# AFE_Pants_Powered.net
KiCad netlist of a schematic drawn in EAGLE
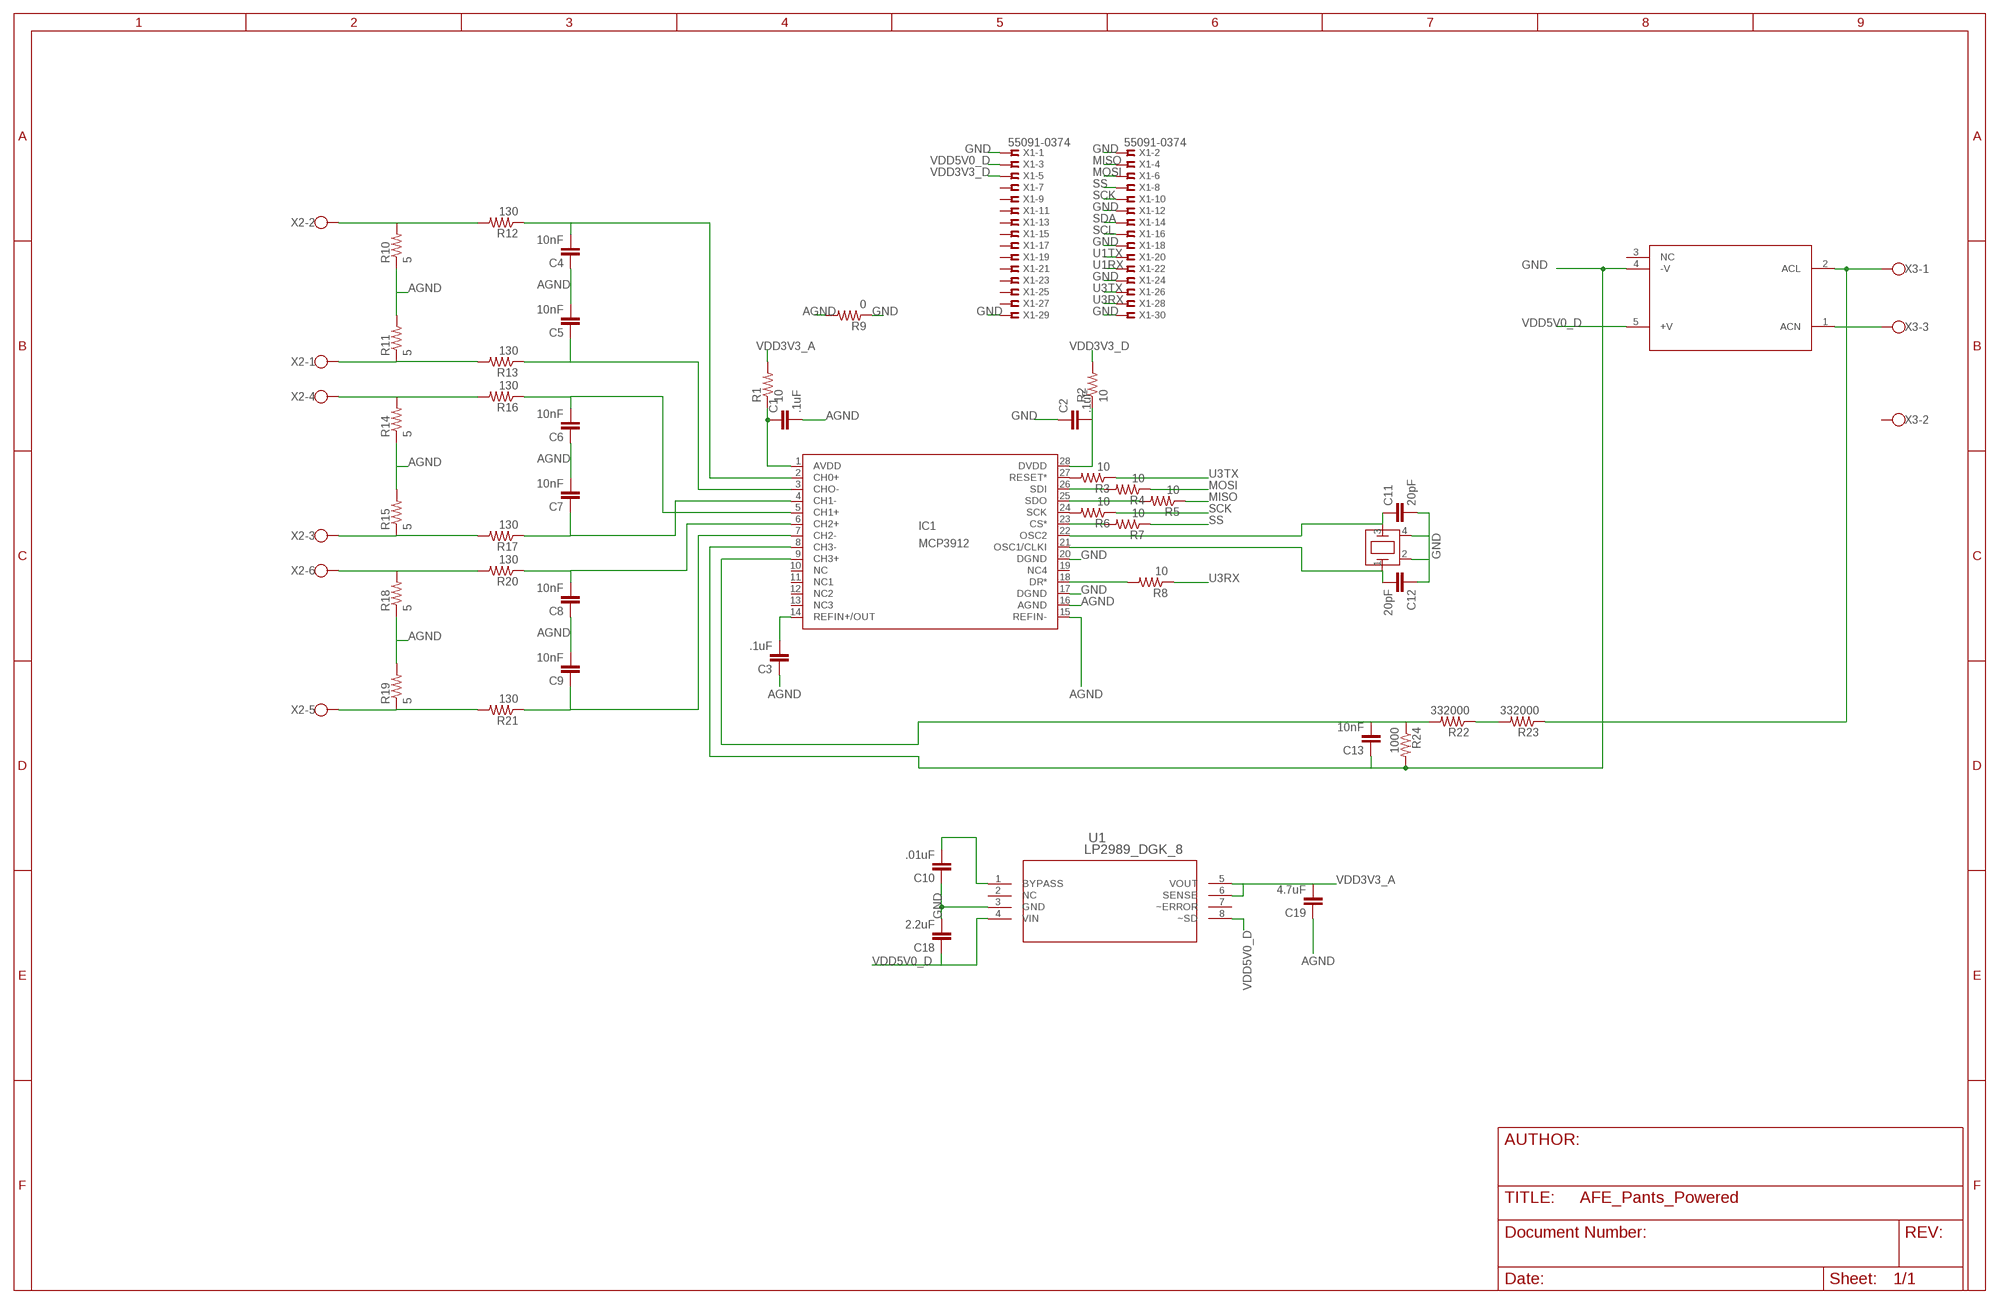
[diagram p0: schematic, sheet 1]

(export (version "E")
  (design (tool "Eeschema 10.0.6"))
  (components
    (comp (ref "C1")
      (value ".1uF")
      (footprint "eagle-import:0805")
      (libsource (lib "eagle-import") (part "CAP0805"))
    )
    (comp (ref "C2")
      (value ".1uF")
      (footprint "eagle-import:0805")
      (libsource (lib "eagle-import") (part "CAP0805"))
    )
    (comp (ref "C3")
      (value ".1uF")
      (footprint "eagle-import:0805")
      (libsource (lib "eagle-import") (part "CAP0805"))
    )
    (comp (ref "C4")
      (value "10nF")
      (footprint "eagle-import:0805")
      (libsource (lib "eagle-import") (part "CAP0805"))
    )
    (comp (ref "C5")
      (value "10nF")
      (footprint "eagle-import:0805")
      (libsource (lib "eagle-import") (part "CAP0805"))
    )
    (comp (ref "C6")
      (value "10nF")
      (footprint "eagle-import:0805")
      (libsource (lib "eagle-import") (part "CAP0805"))
    )
    (comp (ref "C7")
      (value "10nF")
      (footprint "eagle-import:0805")
      (libsource (lib "eagle-import") (part "CAP0805"))
    )
    (comp (ref "C8")
      (value "10nF")
      (footprint "eagle-import:0805")
      (libsource (lib "eagle-import") (part "CAP0805"))
    )
    (comp (ref "C9")
      (value "10nF")
      (footprint "eagle-import:0805")
      (libsource (lib "eagle-import") (part "CAP0805"))
    )
    (comp (ref "C10")
      (value ".01uF")
      (footprint "eagle-import:0805")
      (libsource (lib "eagle-import") (part "CAP0805"))
    )
    (comp (ref "C11")
      (value "20pF")
      (footprint "eagle-import:0805")
      (libsource (lib "eagle-import") (part "CAP0805"))
    )
    (comp (ref "C12")
      (value "20pF")
      (footprint "eagle-import:0805")
      (libsource (lib "eagle-import") (part "CAP0805"))
    )
    (comp (ref "C13")
      (value "10nF")
      (footprint "eagle-import:0805")
      (libsource (lib "eagle-import") (part "CAP0805"))
    )
    (comp (ref "C18")
      (value "2.2uF")
      (footprint "eagle-import:0805")
      (libsource (lib "eagle-import") (part "CAP0805"))
    )
    (comp (ref "C19")
      (value "4.7uF")
      (footprint "eagle-import:0805")
      (libsource (lib "eagle-import") (part "CAP0805"))
    )
    (comp (ref "IC1")
      (value "MCP3912")
      (footprint "eagle-import:SSOP28")
      (libsource (lib "eagle-import") (part "MCP3912"))
    )
    (comp (ref "R1")
      (value "10")
      (footprint "eagle-import:0805")
      (libsource (lib "eagle-import") (part "RESISTOR0805-RES"))
    )
    (comp (ref "R2")
      (value "10")
      (footprint "eagle-import:0805")
      (libsource (lib "eagle-import") (part "RESISTOR0805-RES"))
    )
    (comp (ref "R3")
      (value "10")
      (footprint "eagle-import:0805")
      (libsource (lib "eagle-import") (part "RESISTOR0805-RES"))
    )
    (comp (ref "R4")
      (value "10")
      (footprint "eagle-import:0805")
      (libsource (lib "eagle-import") (part "RESISTOR0805-RES"))
    )
    (comp (ref "R5")
      (value "10")
      (footprint "eagle-import:0805")
      (libsource (lib "eagle-import") (part "RESISTOR0805-RES"))
    )
    (comp (ref "R6")
      (value "10")
      (footprint "eagle-import:0805")
      (libsource (lib "eagle-import") (part "RESISTOR0805-RES"))
    )
    (comp (ref "R7")
      (value "10")
      (footprint "eagle-import:0805")
      (libsource (lib "eagle-import") (part "RESISTOR0805-RES"))
    )
    (comp (ref "R8")
      (value "10")
      (footprint "eagle-import:0805")
      (libsource (lib "eagle-import") (part "RESISTOR0805-RES"))
    )
    (comp (ref "R9")
      (value "0")
      (footprint "eagle-import:0805")
      (libsource (lib "eagle-import") (part "RESISTOR0805-RES"))
    )
    (comp (ref "R10")
      (value "5")
      (footprint "eagle-import:0805")
      (libsource (lib "eagle-import") (part "RESISTOR0805-RES"))
    )
    (comp (ref "R11")
      (value "5")
      (footprint "eagle-import:0805")
      (libsource (lib "eagle-import") (part "RESISTOR0805-RES"))
    )
    (comp (ref "R12")
      (value "130")
      (footprint "eagle-import:0805")
      (libsource (lib "eagle-import") (part "RESISTOR0805-RES"))
    )
    (comp (ref "R13")
      (value "130")
      (footprint "eagle-import:0805")
      (libsource (lib "eagle-import") (part "RESISTOR0805-RES"))
    )
    (comp (ref "R14")
      (value "5")
      (footprint "eagle-import:0805")
      (libsource (lib "eagle-import") (part "RESISTOR0805-RES"))
    )
    (comp (ref "R15")
      (value "5")
      (footprint "eagle-import:0805")
      (libsource (lib "eagle-import") (part "RESISTOR0805-RES"))
    )
    (comp (ref "R16")
      (value "130")
      (footprint "eagle-import:0805")
      (libsource (lib "eagle-import") (part "RESISTOR0805-RES"))
    )
    (comp (ref "R17")
      (value "130")
      (footprint "eagle-import:0805")
      (libsource (lib "eagle-import") (part "RESISTOR0805-RES"))
    )
    (comp (ref "R18")
      (value "5")
      (footprint "eagle-import:0805")
      (libsource (lib "eagle-import") (part "RESISTOR0805-RES"))
    )
    (comp (ref "R19")
      (value "5")
      (footprint "eagle-import:0805")
      (libsource (lib "eagle-import") (part "RESISTOR0805-RES"))
    )
    (comp (ref "R20")
      (value "130")
      (footprint "eagle-import:0805")
      (libsource (lib "eagle-import") (part "RESISTOR0805-RES"))
    )
    (comp (ref "R21")
      (value "130")
      (footprint "eagle-import:0805")
      (libsource (lib "eagle-import") (part "RESISTOR0805-RES"))
    )
    (comp (ref "R22")
      (value "332000")
      (footprint "eagle-import:0805")
      (libsource (lib "eagle-import") (part "RESISTOR0805-RES"))
    )
    (comp (ref "R23")
      (value "332000")
      (footprint "eagle-import:0805")
      (libsource (lib "eagle-import") (part "RESISTOR0805-RES"))
    )
    (comp (ref "R24")
      (value "1000")
      (footprint "eagle-import:0805")
      (libsource (lib "eagle-import") (part "RESISTOR0805-RES"))
    )
    (comp (ref "U$1")
      (value "7M-12.000MEEQ-T")
      (footprint "eagle-import:7M-CRYSTAL")
      (libsource (lib "eagle-import") (part "7M-12.000MEEQ-T"))
    )
    (comp (ref "U$2")
      (value "ECE05US05")
      (footprint "eagle-import:ECE05US05")
      (libsource (lib "eagle-import") (part "ECE05US05"))
    )
    (comp (ref "U1")
      (value "LP2989_DGK_8")
      (footprint "eagle-import:MUA08A")
      (fields (field (name "PARTNUMBER") "LP2989AIMM-25"))
      (libsource (lib "eagle-import") (part "LP2989_DGK_8"))
    )
    (comp (ref "X1")
      (value "55091-0374")
      (footprint "eagle-import:55091-0374")
      (libsource (lib "eagle-import") (part "55091-0374"))
    )
    (comp (ref "X2")
      (value "W237-6")
      (footprint "eagle-import:W237-6")
      (libsource (lib "eagle-import") (part "W237-6"))
    )
    (comp (ref "X3")
      (value "W237-103")
      (footprint "eagle-import:W237-103")
      (fields (field (name "MPN") "237-103"))
      (libsource (lib "eagle-import") (part "W237-103"))
    )
  )
  (nets
    (net (code "1") (name "/AGND") (class "Default")
      (node (ref "C1") (pin "2") (pinfunction "2_2") (pintype "passive"))
      (node (ref "C19") (pin "1") (pinfunction "1_1") (pintype "passive"))
      (node (ref "C3") (pin "1") (pinfunction "1_1") (pintype "passive"))
      (node (ref "C4") (pin "1") (pinfunction "1_1") (pintype "passive"))
      (node (ref "C5") (pin "2") (pinfunction "2_2") (pintype "passive"))
      (node (ref "C6") (pin "1") (pinfunction "1_1") (pintype "passive"))
      (node (ref "C7") (pin "2") (pinfunction "2_2") (pintype "passive"))
      (node (ref "C8") (pin "1") (pinfunction "1_1") (pintype "passive"))
      (node (ref "C9") (pin "2") (pinfunction "2_2") (pintype "passive"))
      (node (ref "IC1") (pin "15") (pinfunction "REFIN-_15") (pintype "bidirectional"))
      (node (ref "IC1") (pin "16") (pinfunction "AGND_16") (pintype "bidirectional"))
      (node (ref "R10") (pin "1") (pinfunction "1_1") (pintype "passive"))
      (node (ref "R11") (pin "2") (pinfunction "2_2") (pintype "passive"))
      (node (ref "R14") (pin "1") (pinfunction "1_1") (pintype "passive"))
      (node (ref "R15") (pin "2") (pinfunction "2_2") (pintype "passive"))
      (node (ref "R18") (pin "1") (pinfunction "1_1") (pintype "passive"))
      (node (ref "R19") (pin "2") (pinfunction "2_2") (pintype "passive"))
      (node (ref "R9") (pin "2") (pinfunction "2_2") (pintype "passive"))
    )
    (net (code "2") (name "/GND") (class "Default")
      (node (ref "C10") (pin "1") (pinfunction "1_1") (pintype "passive"))
      (node (ref "C11") (pin "2") (pinfunction "2_2") (pintype "passive"))
      (node (ref "C12") (pin "1") (pinfunction "1_1") (pintype "passive"))
      (node (ref "C13") (pin "1") (pinfunction "1_1") (pintype "passive"))
      (node (ref "C18") (pin "2") (pinfunction "2_2") (pintype "passive"))
      (node (ref "C2") (pin "1") (pinfunction "1_1") (pintype "passive"))
      (node (ref "IC1") (pin "17") (pinfunction "DGND_17") (pintype "bidirectional"))
      (node (ref "IC1") (pin "20") (pinfunction "DGND_20") (pintype "bidirectional"))
      (node (ref "IC1") (pin "8") (pinfunction "CH3-_8") (pintype "bidirectional"))
      (node (ref "R24") (pin "2") (pinfunction "2_2") (pintype "passive"))
      (node (ref "R9") (pin "1") (pinfunction "1_1") (pintype "passive"))
      (node (ref "U$1") (pin "2") (pinfunction "GND1_2") (pintype "bidirectional"))
      (node (ref "U$1") (pin "4") (pinfunction "GND2_4") (pintype "bidirectional"))
      (node (ref "U$2") (pin "4") (pinfunction "-V_4") (pintype "bidirectional"))
      (node (ref "U1") (pin "3") (pinfunction "GND_3") (pintype "passive"))
      (node (ref "X1") (pin "1") (pinfunction "S_1") (pintype "passive"))
      (node (ref "X1") (pin "12") (pinfunction "S_12") (pintype "passive"))
      (node (ref "X1") (pin "18") (pinfunction "S_18") (pintype "passive"))
      (node (ref "X1") (pin "2") (pinfunction "S_2") (pintype "passive"))
      (node (ref "X1") (pin "24") (pinfunction "S_24") (pintype "passive"))
      (node (ref "X1") (pin "29") (pinfunction "S_29") (pintype "passive"))
      (node (ref "X1") (pin "30") (pinfunction "S_30") (pintype "passive"))
    )
    (net (code "3") (name "/MISO") (class "Default")
      (node (ref "R5") (pin "1") (pinfunction "1_1") (pintype "passive"))
      (node (ref "X1") (pin "4") (pinfunction "S_4") (pintype "passive"))
    )
    (net (code "4") (name "/MOSI") (class "Default")
      (node (ref "R4") (pin "1") (pinfunction "1_1") (pintype "passive"))
      (node (ref "X1") (pin "6") (pinfunction "S_6") (pintype "passive"))
    )
    (net (code "5") (name "/SCK") (class "Default")
      (node (ref "R6") (pin "1") (pinfunction "1_1") (pintype "passive"))
      (node (ref "X1") (pin "10") (pinfunction "S_10") (pintype "passive"))
    )
    (net (code "6") (name "/SCL") (class "Default")
      (node (ref "X1") (pin "16") (pinfunction "S_16") (pintype "passive"))
    )
    (net (code "7") (name "/SDA") (class "Default")
      (node (ref "X1") (pin "14") (pinfunction "S_14") (pintype "passive"))
    )
    (net (code "8") (name "/SS") (class "Default")
      (node (ref "R7") (pin "1") (pinfunction "1_1") (pintype "passive"))
      (node (ref "X1") (pin "8") (pinfunction "S_8") (pintype "passive"))
    )
    (net (code "9") (name "/U1RX") (class "Default")
      (node (ref "X1") (pin "22") (pinfunction "S_22") (pintype "passive"))
    )
    (net (code "10") (name "/U1TX") (class "Default")
      (node (ref "X1") (pin "20") (pinfunction "S_20") (pintype "passive"))
    )
    (net (code "11") (name "/U3RX") (class "Default")
      (node (ref "R8") (pin "1") (pinfunction "1_1") (pintype "passive"))
      (node (ref "X1") (pin "28") (pinfunction "S_28") (pintype "passive"))
    )
    (net (code "12") (name "/U3TX") (class "Default")
      (node (ref "R3") (pin "1") (pinfunction "1_1") (pintype "passive"))
      (node (ref "X1") (pin "26") (pinfunction "S_26") (pintype "passive"))
    )
    (net (code "13") (name "/VDD3V3_A") (class "Default")
      (node (ref "C19") (pin "2") (pinfunction "2_2") (pintype "passive"))
      (node (ref "R1") (pin "2") (pinfunction "2_2") (pintype "passive"))
      (node (ref "U1") (pin "5") (pinfunction "VOUT_5") (pintype "output"))
      (node (ref "U1") (pin "6") (pinfunction "SENSE_6") (pintype "passive"))
    )
    (net (code "14") (name "/VDD3V3_D") (class "Default")
      (node (ref "R2") (pin "2") (pinfunction "2_2") (pintype "passive"))
      (node (ref "X1") (pin "5") (pinfunction "S_5") (pintype "passive"))
    )
    (net (code "15") (name "/VDD5V0_D") (class "Default")
      (node (ref "C18") (pin "1") (pinfunction "1_1") (pintype "passive"))
      (node (ref "U$2") (pin "5") (pinfunction "+V_5") (pintype "bidirectional"))
      (node (ref "U1") (pin "4") (pinfunction "VIN_4") (pintype "input"))
      (node (ref "U1") (pin "8") (pinfunction "~{SD}_8") (pintype "passive"))
      (node (ref "X1") (pin "3") (pinfunction "S_3") (pintype "passive"))
    )
    (net (code "16") (name "Net-(IC1-AVDD)") (class "Default")
      (node (ref "C1") (pin "1") (pinfunction "1_1") (pintype "passive"))
      (node (ref "IC1") (pin "1") (pinfunction "AVDD_1") (pintype "bidirectional"))
      (node (ref "R1") (pin "1") (pinfunction "1_1") (pintype "passive"))
    )
    (net (code "17") (name "Net-(IC1-CH0+)") (class "Default")
      (node (ref "C4") (pin "2") (pinfunction "2_2") (pintype "passive"))
      (node (ref "IC1") (pin "2") (pinfunction "CH0+_2") (pintype "bidirectional"))
      (node (ref "R12") (pin "1") (pinfunction "1_1") (pintype "passive"))
    )
    (net (code "18") (name "Net-(IC1-CH1+)") (class "Default")
      (node (ref "C6") (pin "2") (pinfunction "2_2") (pintype "passive"))
      (node (ref "IC1") (pin "5") (pinfunction "CH1+_5") (pintype "bidirectional"))
      (node (ref "R16") (pin "1") (pinfunction "1_1") (pintype "passive"))
    )
    (net (code "19") (name "Net-(IC1-CH1-)") (class "Default")
      (node (ref "C7") (pin "1") (pinfunction "1_1") (pintype "passive"))
      (node (ref "IC1") (pin "4") (pinfunction "CH1-_4") (pintype "bidirectional"))
      (node (ref "R17") (pin "1") (pinfunction "1_1") (pintype "passive"))
    )
    (net (code "20") (name "Net-(IC1-CH2+)") (class "Default")
      (node (ref "C8") (pin "2") (pinfunction "2_2") (pintype "passive"))
      (node (ref "IC1") (pin "6") (pinfunction "CH2+_6") (pintype "bidirectional"))
      (node (ref "R20") (pin "1") (pinfunction "1_1") (pintype "passive"))
    )
    (net (code "21") (name "Net-(IC1-CH2-)") (class "Default")
      (node (ref "C9") (pin "1") (pinfunction "1_1") (pintype "passive"))
      (node (ref "IC1") (pin "7") (pinfunction "CH2-_7") (pintype "bidirectional"))
      (node (ref "R21") (pin "1") (pinfunction "1_1") (pintype "passive"))
    )
    (net (code "22") (name "Net-(IC1-CH3+)") (class "Default")
      (node (ref "C13") (pin "2") (pinfunction "2_2") (pintype "passive"))
      (node (ref "IC1") (pin "9") (pinfunction "CH3+_9") (pintype "bidirectional"))
      (node (ref "R22") (pin "2") (pinfunction "2_2") (pintype "passive"))
      (node (ref "R24") (pin "1") (pinfunction "1_1") (pintype "passive"))
    )
    (net (code "23") (name "Net-(IC1-CHO-)") (class "Default")
      (node (ref "C5") (pin "1") (pinfunction "1_1") (pintype "passive"))
      (node (ref "IC1") (pin "3") (pinfunction "CHO-_3") (pintype "bidirectional"))
      (node (ref "R13") (pin "1") (pinfunction "1_1") (pintype "passive"))
    )
    (net (code "24") (name "Net-(IC1-CS*)") (class "Default")
      (node (ref "IC1") (pin "23") (pinfunction "CS*_23") (pintype "bidirectional"))
      (node (ref "R7") (pin "2") (pinfunction "2_2") (pintype "passive"))
    )
    (net (code "25") (name "Net-(IC1-DR*)") (class "Default")
      (node (ref "IC1") (pin "18") (pinfunction "DR*_18") (pintype "bidirectional"))
      (node (ref "R8") (pin "2") (pinfunction "2_2") (pintype "passive"))
    )
    (net (code "26") (name "Net-(IC1-DVDD)") (class "Default")
      (node (ref "C2") (pin "2") (pinfunction "2_2") (pintype "passive"))
      (node (ref "IC1") (pin "28") (pinfunction "DVDD_28") (pintype "bidirectional"))
      (node (ref "R2") (pin "1") (pinfunction "1_1") (pintype "passive"))
    )
    (net (code "27") (name "Net-(IC1-OSC1{slash}CLKI)") (class "Default")
      (node (ref "C12") (pin "2") (pinfunction "2_2") (pintype "passive"))
      (node (ref "IC1") (pin "21") (pinfunction "OSC1/CLKI_21") (pintype "bidirectional"))
      (node (ref "U$1") (pin "1") (pinfunction "OSC1_1") (pintype "bidirectional"))
    )
    (net (code "28") (name "Net-(IC1-OSC2)") (class "Default")
      (node (ref "C11") (pin "1") (pinfunction "1_1") (pintype "passive"))
      (node (ref "IC1") (pin "22") (pinfunction "OSC2_22") (pintype "bidirectional"))
      (node (ref "U$1") (pin "3") (pinfunction "OSC2_3") (pintype "bidirectional"))
    )
    (net (code "29") (name "Net-(IC1-REFIN+{slash}OUT)") (class "Default")
      (node (ref "C3") (pin "2") (pinfunction "2_2") (pintype "passive"))
      (node (ref "IC1") (pin "14") (pinfunction "REFIN+/OUT_14") (pintype "bidirectional"))
    )
    (net (code "30") (name "Net-(IC1-RESET*)") (class "Default")
      (node (ref "IC1") (pin "27") (pinfunction "RESET*_27") (pintype "bidirectional"))
      (node (ref "R3") (pin "2") (pinfunction "2_2") (pintype "passive"))
    )
    (net (code "31") (name "Net-(IC1-SCK)") (class "Default")
      (node (ref "IC1") (pin "24") (pinfunction "SCK_24") (pintype "bidirectional"))
      (node (ref "R6") (pin "2") (pinfunction "2_2") (pintype "passive"))
    )
    (net (code "32") (name "Net-(IC1-SDI)") (class "Default")
      (node (ref "IC1") (pin "26") (pinfunction "SDI_26") (pintype "bidirectional"))
      (node (ref "R4") (pin "2") (pinfunction "2_2") (pintype "passive"))
    )
    (net (code "33") (name "Net-(IC1-SDO)") (class "Default")
      (node (ref "IC1") (pin "25") (pinfunction "SDO_25") (pintype "bidirectional"))
      (node (ref "R5") (pin "2") (pinfunction "2_2") (pintype "passive"))
    )
    (net (code "34") (name "Net-(R22-Pad1)") (class "Default")
      (node (ref "R22") (pin "1") (pinfunction "1_1") (pintype "passive"))
      (node (ref "R23") (pin "2") (pinfunction "2_2") (pintype "passive"))
    )
    (net (code "35") (name "Net-(U$2-ACL)") (class "Default")
      (node (ref "R23") (pin "1") (pinfunction "1_1") (pintype "passive"))
      (node (ref "U$2") (pin "2") (pinfunction "ACL_2") (pintype "bidirectional"))
      (node (ref "X3") (pin "1") (pinfunction "KL_1") (pintype "passive"))
    )
    (net (code "36") (name "Net-(U$2-ACN)") (class "Default")
      (node (ref "U$2") (pin "1") (pinfunction "ACN_1") (pintype "bidirectional"))
      (node (ref "X3") (pin "3") (pinfunction "KL_3") (pintype "passive"))
    )
    (net (code "37") (name "Net-(U1-BYPASS)") (class "Default")
      (node (ref "C10") (pin "2") (pinfunction "2_2") (pintype "passive"))
      (node (ref "U1") (pin "1") (pinfunction "BYPASS_1") (pintype "passive"))
    )
    (net (code "38") (name "Net-(X2A-KL)") (class "Default")
      (node (ref "R11") (pin "1") (pinfunction "1_1") (pintype "passive"))
      (node (ref "R13") (pin "2") (pinfunction "2_2") (pintype "passive"))
      (node (ref "X2") (pin "1") (pinfunction "KL_1") (pintype "passive"))
    )
    (net (code "39") (name "Net-(X2B-KL)") (class "Default")
      (node (ref "R10") (pin "2") (pinfunction "2_2") (pintype "passive"))
      (node (ref "R12") (pin "2") (pinfunction "2_2") (pintype "passive"))
      (node (ref "X2") (pin "2") (pinfunction "KL_2") (pintype "passive"))
    )
    (net (code "40") (name "Net-(X2C-KL)") (class "Default")
      (node (ref "R15") (pin "1") (pinfunction "1_1") (pintype "passive"))
      (node (ref "R17") (pin "2") (pinfunction "2_2") (pintype "passive"))
      (node (ref "X2") (pin "3") (pinfunction "KL_3") (pintype "passive"))
    )
    (net (code "41") (name "Net-(X2D-KL)") (class "Default")
      (node (ref "R14") (pin "2") (pinfunction "2_2") (pintype "passive"))
      (node (ref "R16") (pin "2") (pinfunction "2_2") (pintype "passive"))
      (node (ref "X2") (pin "4") (pinfunction "KL_4") (pintype "passive"))
    )
    (net (code "42") (name "Net-(X2E-KL)") (class "Default")
      (node (ref "R19") (pin "1") (pinfunction "1_1") (pintype "passive"))
      (node (ref "R21") (pin "2") (pinfunction "2_2") (pintype "passive"))
      (node (ref "X2") (pin "5") (pinfunction "KL_5") (pintype "passive"))
    )
    (net (code "43") (name "Net-(X2F-KL)") (class "Default")
      (node (ref "R18") (pin "2") (pinfunction "2_2") (pintype "passive"))
      (node (ref "R20") (pin "2") (pinfunction "2_2") (pintype "passive"))
      (node (ref "X2") (pin "6") (pinfunction "KL_6") (pintype "passive"))
    )
    (net (code "44") (name "unconnected-(IC1-NC-Pad10)") (class "Default")
      (node (ref "IC1") (pin "10") (pinfunction "NC_10") (pintype "bidirectional"))
    )
    (net (code "45") (name "unconnected-(IC1-NC1-Pad11)") (class "Default")
      (node (ref "IC1") (pin "11") (pinfunction "NC1_11") (pintype "bidirectional"))
    )
    (net (code "46") (name "unconnected-(IC1-NC2-Pad12)") (class "Default")
      (node (ref "IC1") (pin "12") (pinfunction "NC2_12") (pintype "bidirectional"))
    )
    (net (code "47") (name "unconnected-(IC1-NC3-Pad13)") (class "Default")
      (node (ref "IC1") (pin "13") (pinfunction "NC3_13") (pintype "bidirectional"))
    )
    (net (code "48") (name "unconnected-(IC1-NC4-Pad19)") (class "Default")
      (node (ref "IC1") (pin "19") (pinfunction "NC4_19") (pintype "bidirectional"))
    )
    (net (code "49") (name "unconnected-(U$2-NC-Pad3)") (class "Default")
      (node (ref "U$2") (pin "3") (pinfunction "NC_3") (pintype "bidirectional"))
    )
    (net (code "50") (name "unconnected-(U1-NC-Pad2)") (class "Default")
      (node (ref "U1") (pin "2") (pinfunction "NC_2") (pintype "passive"))
    )
    (net (code "51") (name "unconnected-(U1-~{ERROR}-Pad7)") (class "Default")
      (node (ref "U1") (pin "7") (pinfunction "~{ERROR}_7") (pintype "passive"))
    )
    (net (code "52") (name "unconnected-(X1AB-S-Pad7)") (class "Default")
      (node (ref "X1") (pin "7") (pinfunction "S_7") (pintype "passive"))
    )
    (net (code "53") (name "unconnected-(X1AD-S-Pad9)") (class "Default")
      (node (ref "X1") (pin "9") (pinfunction "S_9") (pintype "passive"))
    )
    (net (code "54") (name "unconnected-(X1C-S-Pad11)") (class "Default")
      (node (ref "X1") (pin "11") (pinfunction "S_11") (pintype "passive"))
    )
    (net (code "55") (name "unconnected-(X1E-S-Pad13)") (class "Default")
      (node (ref "X1") (pin "13") (pinfunction "S_13") (pintype "passive"))
    )
    (net (code "56") (name "unconnected-(X1G-S-Pad15)") (class "Default")
      (node (ref "X1") (pin "15") (pinfunction "S_15") (pintype "passive"))
    )
    (net (code "57") (name "unconnected-(X1I-S-Pad17)") (class "Default")
      (node (ref "X1") (pin "17") (pinfunction "S_17") (pintype "passive"))
    )
    (net (code "58") (name "unconnected-(X1K-S-Pad19)") (class "Default")
      (node (ref "X1") (pin "19") (pinfunction "S_19") (pintype "passive"))
    )
    (net (code "59") (name "unconnected-(X1N-S-Pad21)") (class "Default")
      (node (ref "X1") (pin "21") (pinfunction "S_21") (pintype "passive"))
    )
    (net (code "60") (name "unconnected-(X1P-S-Pad23)") (class "Default")
      (node (ref "X1") (pin "23") (pinfunction "S_23") (pintype "passive"))
    )
    (net (code "61") (name "unconnected-(X1R-S-Pad25)") (class "Default")
      (node (ref "X1") (pin "25") (pinfunction "S_25") (pintype "passive"))
    )
    (net (code "62") (name "unconnected-(X1T-S-Pad27)") (class "Default")
      (node (ref "X1") (pin "27") (pinfunction "S_27") (pintype "passive"))
    )
    (net (code "63") (name "unconnected-(X3B-KL-Pad2)") (class "Default")
      (node (ref "X3") (pin "2") (pinfunction "KL_2") (pintype "passive"))
    )
  )
)
